# 5V-and-3V3-ldo.net
KiCad netlist of a schematic drawn in Altium Designer
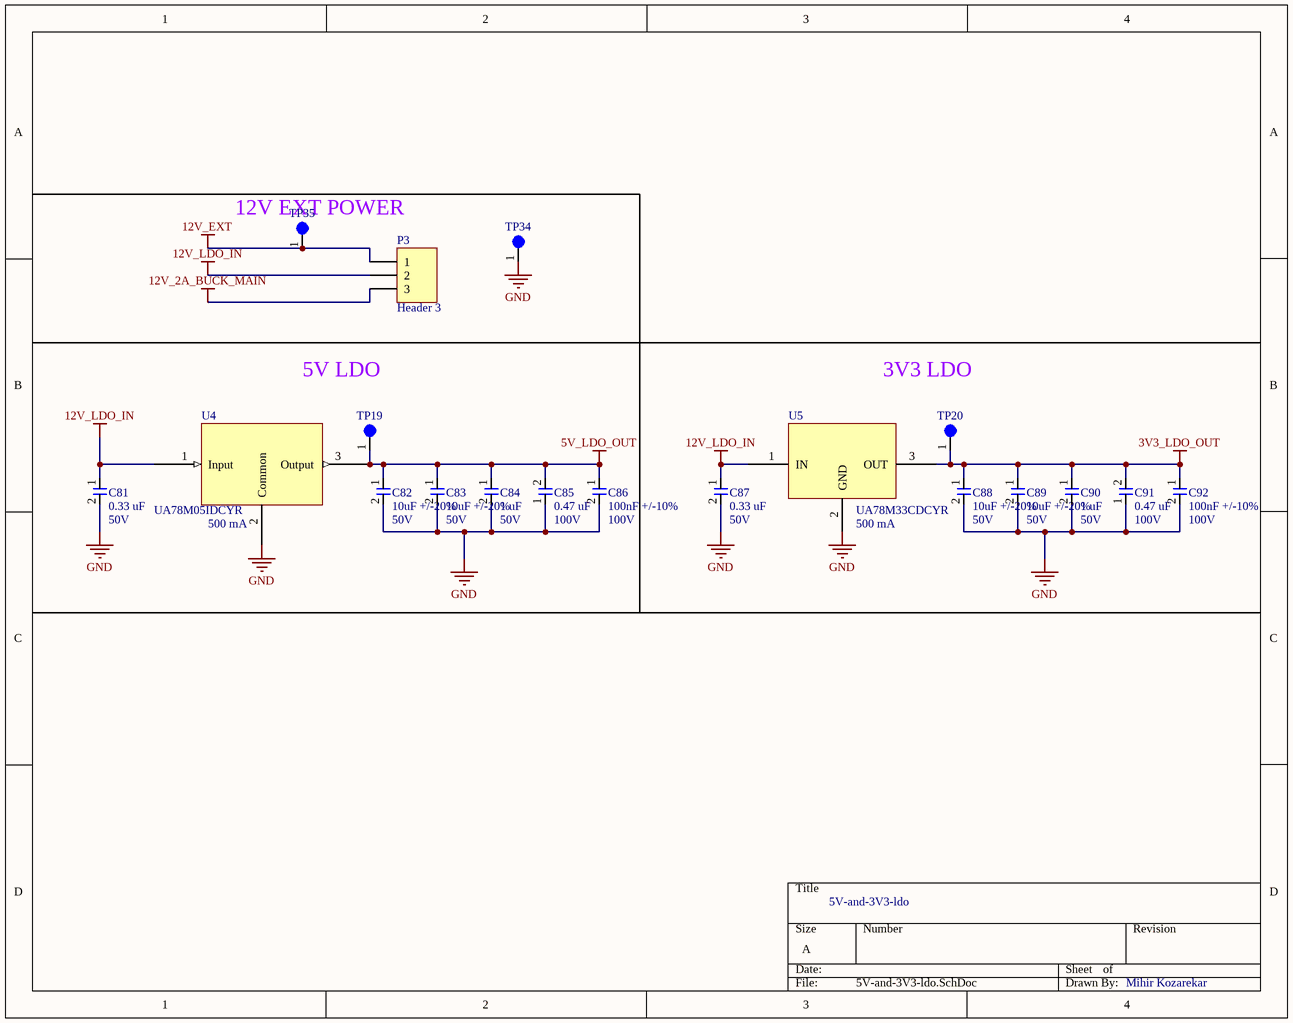
[diagram p0: 5V-and-3V3-ldo.SchDoc]

(export (version "E")
  (design (tool "Eeschema 10.0.6"))
  (components
    (comp (ref "C81")
      (value "CGA3E3X7R1H334K080AB")
      (footprint "CAP-0603")
      (description "0.33 µF ±10% 50V Ceramic Capacitor X7R 0603 (1608 Metric)")
      (fields
        (field (name "MANUFACTURER") "TDK Corporation")
        (field (name "TOLERANCE") "+/- 10%")
        (field (name "CAPACITANCE") "0.33 uF")
        (field (name "VOLTAGE") "50V")
      )
      (libsource (lib "MasterLib") (part "CAP-0.33uF-0001"))
    )
    (comp (ref "C82")
      (value "CL31B106KBHNNNE")
      (footprint "CAP-1206")
      (description "10 µF ±10% 50V Ceramic Capacitor X7R 1206 (3216 Metric)")
      (fields
        (field (name "MANUFACTURER") "Samsung Electro-Mechanics")
        (field (name "CAPACITANCE") "10uF +/-20%")
        (field (name "VOLTAGE RATING") "50V")
      )
      (libsource (lib "MasterLib") (part "CAP-10U-0001"))
    )
    (comp (ref "C83")
      (value "CL31B106KBHNNNE")
      (footprint "CAP-1206")
      (description "10 µF ±10% 50V Ceramic Capacitor X7R 1206 (3216 Metric)")
      (fields
        (field (name "MANUFACTURER") "Samsung Electro-Mechanics")
        (field (name "CAPACITANCE") "10uF +/-20%")
        (field (name "VOLTAGE RATING") "50V")
      )
      (libsource (lib "MasterLib") (part "CAP-10U-0001"))
    )
    (comp (ref "C84")
      (value "UMK107AB7105KA-T")
      (footprint "CAP-0603")
      (description "1 µF ±10% 50V Ceramic Capacitor X7R 0603 (1608 Metric)")
      (fields (field (name "CAPACITANCE") "1 uF") (field (name "VOLTAGE") "50V"))
      (libsource (lib "MasterLib") (part "CAP-1U-0002"))
    )
    (comp (ref "C85")
      (value "KAM21KR72A474KL")
      (footprint "CAP-0805")
      (description "0.47 µF ±10% 100V Ceramic Capacitor X7R 0805 (2012 Metric)")
      (fields
        (field (name "TOLERANCE") "+/- 10%")
        (field (name "CAPACITANCE") "0.47 uF")
        (field (name "VOLTAGE") "100V")
      )
      (libsource (lib "MasterLib") (part "CAP-0.47U-0001"))
    )
    (comp (ref "C86")
      (value "CC0603KRX7R0BB104")
      (footprint "CAP-0603")
      (description "CAP CER 0.1UF 100V X7R 0603")
      (fields
        (field (name "MANUFACTURER") "YAGEO")
        (field (name "CAPACITANCE") "100nF +/-10%")
        (field (name "VOLTAGE RATING") "100V")
      )
      (libsource (lib "MasterLib") (part "CAP-100N-0001"))
    )
    (comp (ref "C87")
      (value "CGA3E3X7R1H334K080AB")
      (footprint "CAP-0603")
      (description "0.33 µF ±10% 50V Ceramic Capacitor X7R 0603 (1608 Metric)")
      (fields
        (field (name "MANUFACTURER") "TDK Corporation")
        (field (name "TOLERANCE") "+/- 10%")
        (field (name "CAPACITANCE") "0.33 uF")
        (field (name "VOLTAGE") "50V")
      )
      (libsource (lib "MasterLib") (part "CAP-0.33uF-0001"))
    )
    (comp (ref "C88")
      (value "CL31B106KBHNNNE")
      (footprint "CAP-1206")
      (description "10 µF ±10% 50V Ceramic Capacitor X7R 1206 (3216 Metric)")
      (fields
        (field (name "MANUFACTURER") "Samsung Electro-Mechanics")
        (field (name "CAPACITANCE") "10uF +/-20%")
        (field (name "VOLTAGE RATING") "50V")
      )
      (libsource (lib "MasterLib") (part "CAP-10U-0001"))
    )
    (comp (ref "C89")
      (value "CL31B106KBHNNNE")
      (footprint "CAP-1206")
      (description "10 µF ±10% 50V Ceramic Capacitor X7R 1206 (3216 Metric)")
      (fields
        (field (name "MANUFACTURER") "Samsung Electro-Mechanics")
        (field (name "CAPACITANCE") "10uF +/-20%")
        (field (name "VOLTAGE RATING") "50V")
      )
      (libsource (lib "MasterLib") (part "CAP-10U-0001"))
    )
    (comp (ref "C90")
      (value "UMK107AB7105KA-T")
      (footprint "CAP-0603")
      (description "1 µF ±10% 50V Ceramic Capacitor X7R 0603 (1608 Metric)")
      (fields (field (name "CAPACITANCE") "1 uF") (field (name "VOLTAGE") "50V"))
      (libsource (lib "MasterLib") (part "CAP-1U-0002"))
    )
    (comp (ref "C91")
      (value "KAM21KR72A474KL")
      (footprint "CAP-0805")
      (description "0.47 µF ±10% 100V Ceramic Capacitor X7R 0805 (2012 Metric)")
      (fields
        (field (name "TOLERANCE") "+/- 10%")
        (field (name "CAPACITANCE") "0.47 uF")
        (field (name "VOLTAGE") "100V")
      )
      (libsource (lib "MasterLib") (part "CAP-0.47U-0001"))
    )
    (comp (ref "C92")
      (value "CC0603KRX7R0BB104")
      (footprint "CAP-0603")
      (description "CAP CER 0.1UF 100V X7R 0603")
      (fields
        (field (name "MANUFACTURER") "YAGEO")
        (field (name "CAPACITANCE") "100nF +/-10%")
        (field (name "VOLTAGE RATING") "100V")
      )
      (libsource (lib "MasterLib") (part "CAP-100N-0001"))
    )
    (comp (ref "P3")
      (value "Header 3")
      (footprint "HDR1X3")
      (description "Header, 3-Pin")
      (fields (field (name "PUBLISHER") "Altium Limited"))
      (libsource (lib "Miscellaneous Connectors") (part "Header 3"))
    )
    (comp (ref "TP19")
      (value "5003")
      (footprint "TEST-POINT-0001")
      (description "Oranange PC Test Point, Miniature Phoisphor Bronze Silver Plating Through Hole Mounting Type")
      (libsource (lib "MasterLib") (part "TEST-POINT-0001"))
    )
    (comp (ref "TP20")
      (value "5003")
      (footprint "TEST-POINT-0001")
      (description "Oranange PC Test Point, Miniature Phoisphor Bronze Silver Plating Through Hole Mounting Type")
      (libsource (lib "MasterLib") (part "TEST-POINT-0001"))
    )
    (comp (ref "TP34")
      (value "5003")
      (footprint "TEST-POINT-0001")
      (description "Oranange PC Test Point, Miniature Phoisphor Bronze Silver Plating Through Hole Mounting Type")
      (libsource (lib "MasterLib") (part "TEST-POINT-0001"))
    )
    (comp (ref "TP35")
      (value "5003")
      (footprint "TEST-POINT-0001")
      (description "Oranange PC Test Point, Miniature Phoisphor Bronze Silver Plating Through Hole Mounting Type")
      (libsource (lib "MasterLib") (part "TEST-POINT-0001"))
    )
    (comp (ref "U4")
      (value "UA78M05IDCYR")
      (footprint "IC-SOT-223-4")
      (description "Linear Voltage Regulator IC Positive Fixed 1 Output 500mA SOT-223-4")
      (fields (field (name "MANUFACTURER") "Texas Instruments") (field (name "CURRENT") "500 mA"))
      (libsource (lib "MasterLib") (part "IC-LDO-5V-0003"))
    )
    (comp (ref "U5")
      (value "UA78M33CDCYR")
      (footprint "IC-SOT-223-4")
      (description "Linear Voltage Regulator IC Positive Fixed 1 Output 500mA SOT-223-4")
      (fields (field (name "CURRENT") "500 mA"))
      (libsource (lib "MasterLib") (part "IC-LDO-3.3V-0002"))
    )
  )
  (nets
    (net (code "1") (name "3V3_LDO_OUT") (class "Default")
      (node (ref "C88") (pin "1") (pinfunction "1_1") (pintype "passive"))
      (node (ref "C89") (pin "1") (pinfunction "1_1") (pintype "passive"))
      (node (ref "C90") (pin "1") (pinfunction "1_1") (pintype "passive"))
      (node (ref "C91") (pin "2") (pinfunction "2_2") (pintype "passive"))
      (node (ref "C92") (pin "1") (pinfunction "1_1") (pintype "passive"))
      (node (ref "TP20") (pin "1") (pinfunction "0_1") (pintype "passive"))
      (node (ref "U5") (pin "3") (pinfunction "OUT_3") (pintype "power_in"))
    )
    (net (code "2") (name "5V_LDO_OUT") (class "Default")
      (node (ref "C82") (pin "1") (pinfunction "1_1") (pintype "passive"))
      (node (ref "C83") (pin "1") (pinfunction "1_1") (pintype "passive"))
      (node (ref "C84") (pin "1") (pinfunction "1_1") (pintype "passive"))
      (node (ref "C85") (pin "2") (pinfunction "2_2") (pintype "passive"))
      (node (ref "C86") (pin "1") (pinfunction "1_1") (pintype "passive"))
      (node (ref "TP19") (pin "1") (pinfunction "0_1") (pintype "passive"))
      (node (ref "U4") (pin "3") (pinfunction "Output_3") (pintype "output"))
    )
    (net (code "3") (name "12V_2A_BUCK_MAIN") (class "Default")
      (node (ref "P3") (pin "3") (pinfunction "3_3") (pintype "passive"))
    )
    (net (code "4") (name "12V_EXT") (class "Default")
      (node (ref "P3") (pin "1") (pinfunction "1_1") (pintype "passive"))
      (node (ref "TP35") (pin "1") (pinfunction "0_1") (pintype "passive"))
    )
    (net (code "5") (name "12V_LDO_IN") (class "Default")
      (node (ref "C81") (pin "1") (pinfunction "1_1") (pintype "passive"))
      (node (ref "C87") (pin "1") (pinfunction "1_1") (pintype "passive"))
      (node (ref "P3") (pin "2") (pinfunction "2_2") (pintype "passive"))
      (node (ref "U4") (pin "1") (pinfunction "Input_1") (pintype "input"))
      (node (ref "U5") (pin "1") (pinfunction "IN_1") (pintype "power_in"))
    )
    (net (code "6") (name "GND") (class "Default")
      (node (ref "C81") (pin "2") (pinfunction "2_2") (pintype "passive"))
      (node (ref "C82") (pin "2") (pinfunction "2_2") (pintype "passive"))
      (node (ref "C83") (pin "2") (pinfunction "2_2") (pintype "passive"))
      (node (ref "C84") (pin "2") (pinfunction "2_2") (pintype "passive"))
      (node (ref "C85") (pin "1") (pinfunction "1_1") (pintype "passive"))
      (node (ref "C86") (pin "2") (pinfunction "2_2") (pintype "passive"))
      (node (ref "C87") (pin "2") (pinfunction "2_2") (pintype "passive"))
      (node (ref "C88") (pin "2") (pinfunction "2_2") (pintype "passive"))
      (node (ref "C89") (pin "2") (pinfunction "2_2") (pintype "passive"))
      (node (ref "C90") (pin "2") (pinfunction "2_2") (pintype "passive"))
      (node (ref "C91") (pin "1") (pinfunction "1_1") (pintype "passive"))
      (node (ref "C92") (pin "2") (pinfunction "2_2") (pintype "passive"))
      (node (ref "TP34") (pin "1") (pinfunction "0_1") (pintype "passive"))
      (node (ref "U4") (pin "2") (pinfunction "Common_2") (pintype "power_in"))
      (node (ref "U5") (pin "2") (pinfunction "GND_2") (pintype "power_in"))
    )
  )
)
